# SCH_Timer_2026-05-08.net
KiCad netlist of a schematic drawn in EasyEDA
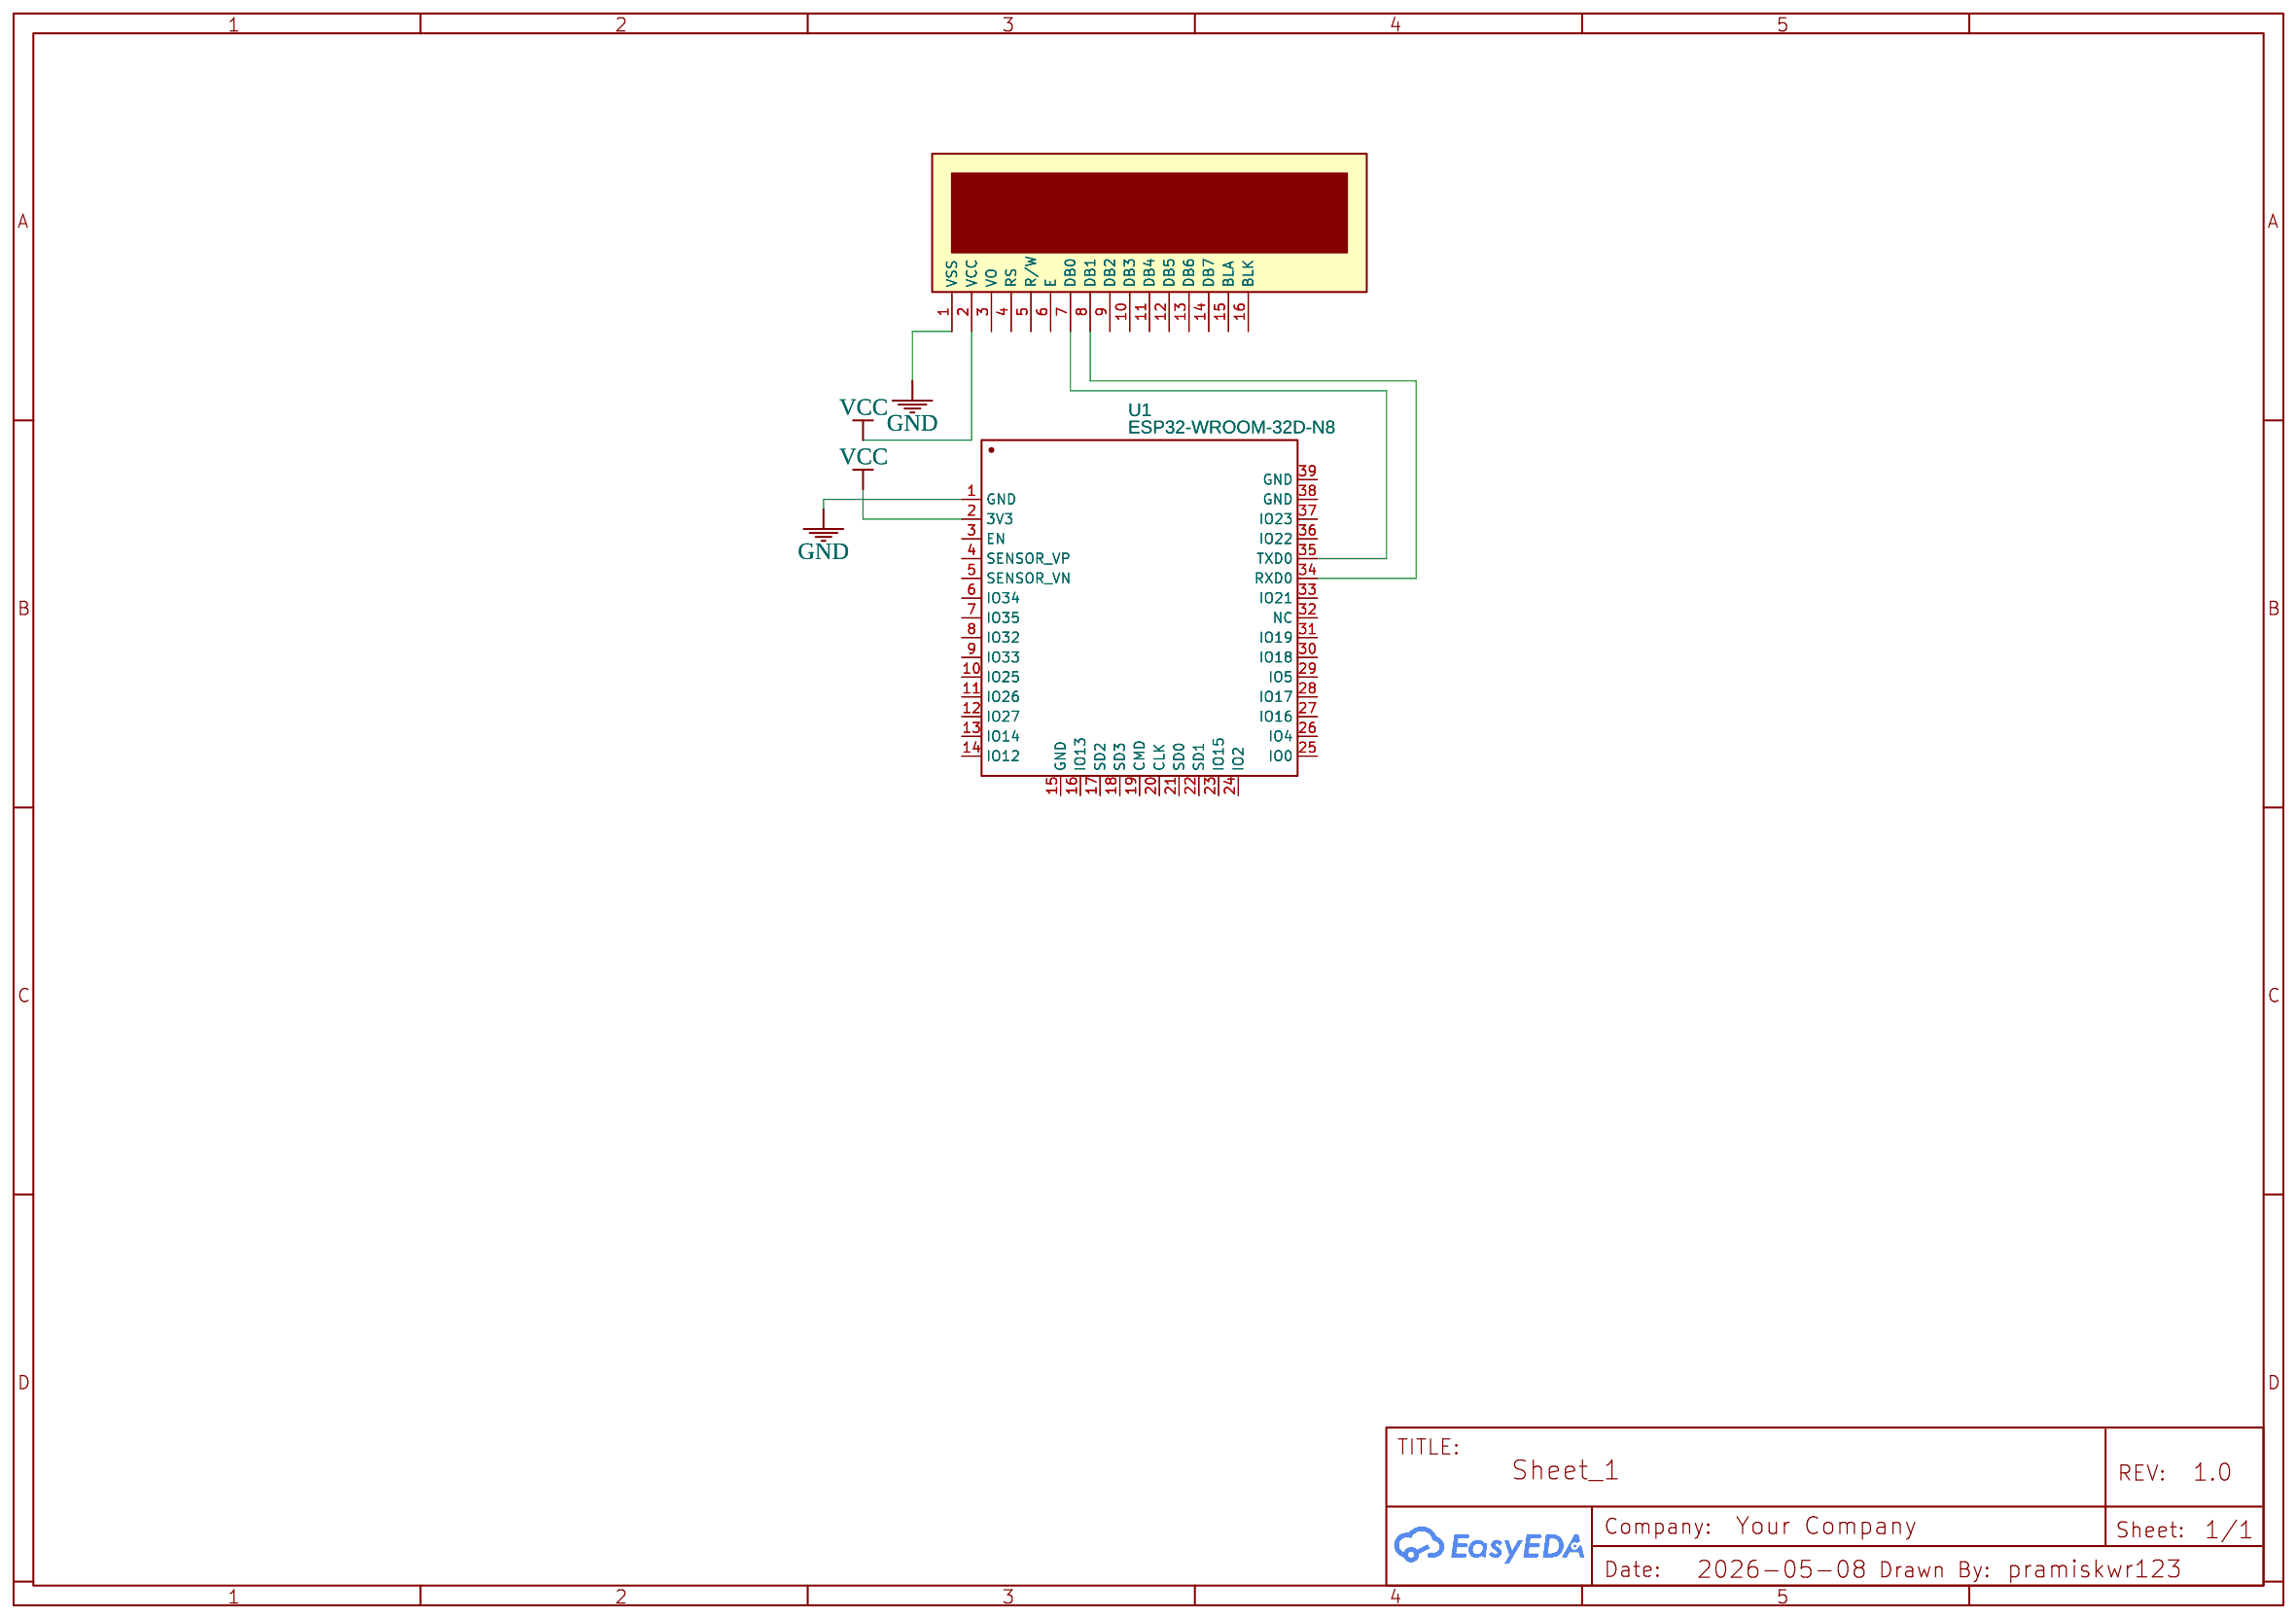
[diagram p0: schematic sheet]

(export (version "E")
  (design (tool "Eeschema 10.0.6"))
  (components
    (comp (ref "LCD1")
      (value "LCD1602")
      (fields
        (field (name "Manufacturer Part") "LCM1602K-NSW-BBW")
        (field (name "Manufacturer") "LONTECH(厦门龙特)")
      )
      (libsource (lib "") (part "LCD1602"))
    )
    (comp (ref "U1")
      (value "ESP32-WROOM-32D-N8")
      (fields (field (name "Manufacturer Part") "ESP32-WROOM-32D-N8-被合并"))
      (libsource (lib "") (part "ESP32-WROOM-32D-N8"))
    )
  )
  (nets
    (net (code "1") (name "GND") (class "Default")
      (node (ref "LCD1") (pin "1") (pinfunction "VSS_1") (pintype "unspecified"))
      (node (ref "U1") (pin "1") (pinfunction "GND_1") (pintype "unspecified"))
    )
    (net (code "2") (name "Net-(LCD1-DB0)") (class "Default")
      (node (ref "LCD1") (pin "7") (pinfunction "DB0_7") (pintype "unspecified"))
      (node (ref "U1") (pin "35") (pinfunction "TXD0_35") (pintype "unspecified"))
    )
    (net (code "3") (name "Net-(LCD1-DB1)") (class "Default")
      (node (ref "LCD1") (pin "8") (pinfunction "DB1_8") (pintype "unspecified"))
      (node (ref "U1") (pin "34") (pinfunction "RXD0_34") (pintype "unspecified"))
    )
    (net (code "4") (name "VCC") (class "Default")
      (node (ref "LCD1") (pin "2") (pinfunction "VCC_2") (pintype "unspecified"))
      (node (ref "U1") (pin "2") (pinfunction "3V3_2") (pintype "unspecified"))
    )
    (net (code "5") (name "unconnected-(LCD1-BLA-Pad15)") (class "Default")
      (node (ref "LCD1") (pin "15") (pinfunction "BLA_15") (pintype "unspecified"))
    )
    (net (code "6") (name "unconnected-(LCD1-BLK-Pad16)") (class "Default")
      (node (ref "LCD1") (pin "16") (pinfunction "BLK_16") (pintype "unspecified"))
    )
    (net (code "7") (name "unconnected-(LCD1-DB2-Pad9)") (class "Default")
      (node (ref "LCD1") (pin "9") (pinfunction "DB2_9") (pintype "unspecified"))
    )
    (net (code "8") (name "unconnected-(LCD1-DB3-Pad10)") (class "Default")
      (node (ref "LCD1") (pin "10") (pinfunction "DB3_10") (pintype "unspecified"))
    )
    (net (code "9") (name "unconnected-(LCD1-DB4-Pad11)") (class "Default")
      (node (ref "LCD1") (pin "11") (pinfunction "DB4_11") (pintype "unspecified"))
    )
    (net (code "10") (name "unconnected-(LCD1-DB5-Pad12)") (class "Default")
      (node (ref "LCD1") (pin "12") (pinfunction "DB5_12") (pintype "unspecified"))
    )
    (net (code "11") (name "unconnected-(LCD1-DB6-Pad13)") (class "Default")
      (node (ref "LCD1") (pin "13") (pinfunction "DB6_13") (pintype "unspecified"))
    )
    (net (code "12") (name "unconnected-(LCD1-DB7-Pad14)") (class "Default")
      (node (ref "LCD1") (pin "14") (pinfunction "DB7_14") (pintype "unspecified"))
    )
    (net (code "13") (name "unconnected-(LCD1-E-Pad6)") (class "Default")
      (node (ref "LCD1") (pin "6") (pinfunction "E_6") (pintype "unspecified"))
    )
    (net (code "14") (name "unconnected-(LCD1-RS-Pad4)") (class "Default")
      (node (ref "LCD1") (pin "4") (pinfunction "RS_4") (pintype "unspecified"))
    )
    (net (code "15") (name "unconnected-(LCD1-R{slash}W-Pad5)") (class "Default")
      (node (ref "LCD1") (pin "5") (pinfunction "R/W_5") (pintype "unspecified"))
    )
    (net (code "16") (name "unconnected-(LCD1-VO-Pad3)") (class "Default")
      (node (ref "LCD1") (pin "3") (pinfunction "VO_3") (pintype "unspecified"))
    )
    (net (code "17") (name "unconnected-(U1-CLK-Pad20)") (class "Default")
      (node (ref "U1") (pin "20") (pinfunction "CLK_20") (pintype "unspecified"))
    )
    (net (code "18") (name "unconnected-(U1-CMD-Pad19)") (class "Default")
      (node (ref "U1") (pin "19") (pinfunction "CMD_19") (pintype "unspecified"))
    )
    (net (code "19") (name "unconnected-(U1-EN-Pad3)") (class "Default")
      (node (ref "U1") (pin "3") (pinfunction "EN_3") (pintype "unspecified"))
    )
    (net (code "20") (name "unconnected-(U1-GND-Pad15)") (class "Default")
      (node (ref "U1") (pin "15") (pinfunction "GND_15") (pintype "unspecified"))
    )
    (net (code "21") (name "unconnected-(U1-GND-Pad38)") (class "Default")
      (node (ref "U1") (pin "38") (pinfunction "GND_38") (pintype "unspecified"))
    )
    (net (code "22") (name "unconnected-(U1-GND-Pad39)") (class "Default")
      (node (ref "U1") (pin "39") (pinfunction "GND_39") (pintype "unspecified"))
    )
    (net (code "23") (name "unconnected-(U1-IO0-Pad25)") (class "Default")
      (node (ref "U1") (pin "25") (pinfunction "IO0_25") (pintype "unspecified"))
    )
    (net (code "24") (name "unconnected-(U1-IO2-Pad24)") (class "Default")
      (node (ref "U1") (pin "24") (pinfunction "IO2_24") (pintype "unspecified"))
    )
    (net (code "25") (name "unconnected-(U1-IO4-Pad26)") (class "Default")
      (node (ref "U1") (pin "26") (pinfunction "IO4_26") (pintype "unspecified"))
    )
    (net (code "26") (name "unconnected-(U1-IO5-Pad29)") (class "Default")
      (node (ref "U1") (pin "29") (pinfunction "IO5_29") (pintype "unspecified"))
    )
    (net (code "27") (name "unconnected-(U1-IO12-Pad14)") (class "Default")
      (node (ref "U1") (pin "14") (pinfunction "IO12_14") (pintype "unspecified"))
    )
    (net (code "28") (name "unconnected-(U1-IO13-Pad16)") (class "Default")
      (node (ref "U1") (pin "16") (pinfunction "IO13_16") (pintype "unspecified"))
    )
    (net (code "29") (name "unconnected-(U1-IO14-Pad13)") (class "Default")
      (node (ref "U1") (pin "13") (pinfunction "IO14_13") (pintype "unspecified"))
    )
    (net (code "30") (name "unconnected-(U1-IO15-Pad23)") (class "Default")
      (node (ref "U1") (pin "23") (pinfunction "IO15_23") (pintype "unspecified"))
    )
    (net (code "31") (name "unconnected-(U1-IO16-Pad27)") (class "Default")
      (node (ref "U1") (pin "27") (pinfunction "IO16_27") (pintype "unspecified"))
    )
    (net (code "32") (name "unconnected-(U1-IO17-Pad28)") (class "Default")
      (node (ref "U1") (pin "28") (pinfunction "IO17_28") (pintype "unspecified"))
    )
    (net (code "33") (name "unconnected-(U1-IO18-Pad30)") (class "Default")
      (node (ref "U1") (pin "30") (pinfunction "IO18_30") (pintype "unspecified"))
    )
    (net (code "34") (name "unconnected-(U1-IO19-Pad31)") (class "Default")
      (node (ref "U1") (pin "31") (pinfunction "IO19_31") (pintype "unspecified"))
    )
    (net (code "35") (name "unconnected-(U1-IO21-Pad33)") (class "Default")
      (node (ref "U1") (pin "33") (pinfunction "IO21_33") (pintype "unspecified"))
    )
    (net (code "36") (name "unconnected-(U1-IO22-Pad36)") (class "Default")
      (node (ref "U1") (pin "36") (pinfunction "IO22_36") (pintype "unspecified"))
    )
    (net (code "37") (name "unconnected-(U1-IO23-Pad37)") (class "Default")
      (node (ref "U1") (pin "37") (pinfunction "IO23_37") (pintype "unspecified"))
    )
    (net (code "38") (name "unconnected-(U1-IO25-Pad10)") (class "Default")
      (node (ref "U1") (pin "10") (pinfunction "IO25_10") (pintype "unspecified"))
    )
    (net (code "39") (name "unconnected-(U1-IO26-Pad11)") (class "Default")
      (node (ref "U1") (pin "11") (pinfunction "IO26_11") (pintype "unspecified"))
    )
    (net (code "40") (name "unconnected-(U1-IO27-Pad12)") (class "Default")
      (node (ref "U1") (pin "12") (pinfunction "IO27_12") (pintype "unspecified"))
    )
    (net (code "41") (name "unconnected-(U1-IO32-Pad8)") (class "Default")
      (node (ref "U1") (pin "8") (pinfunction "IO32_8") (pintype "unspecified"))
    )
    (net (code "42") (name "unconnected-(U1-IO33-Pad9)") (class "Default")
      (node (ref "U1") (pin "9") (pinfunction "IO33_9") (pintype "unspecified"))
    )
    (net (code "43") (name "unconnected-(U1-IO34-Pad6)") (class "Default")
      (node (ref "U1") (pin "6") (pinfunction "IO34_6") (pintype "unspecified"))
    )
    (net (code "44") (name "unconnected-(U1-IO35-Pad7)") (class "Default")
      (node (ref "U1") (pin "7") (pinfunction "IO35_7") (pintype "unspecified"))
    )
    (net (code "45") (name "unconnected-(U1-NC-Pad32)") (class "Default")
      (node (ref "U1") (pin "32") (pinfunction "NC_32") (pintype "unspecified"))
    )
    (net (code "46") (name "unconnected-(U1-SD0-Pad21)") (class "Default")
      (node (ref "U1") (pin "21") (pinfunction "SD0_21") (pintype "unspecified"))
    )
    (net (code "47") (name "unconnected-(U1-SD1-Pad22)") (class "Default")
      (node (ref "U1") (pin "22") (pinfunction "SD1_22") (pintype "unspecified"))
    )
    (net (code "48") (name "unconnected-(U1-SD2-Pad17)") (class "Default")
      (node (ref "U1") (pin "17") (pinfunction "SD2_17") (pintype "unspecified"))
    )
    (net (code "49") (name "unconnected-(U1-SD3-Pad18)") (class "Default")
      (node (ref "U1") (pin "18") (pinfunction "SD3_18") (pintype "unspecified"))
    )
    (net (code "50") (name "unconnected-(U1-SENSOR_VN-Pad5)") (class "Default")
      (node (ref "U1") (pin "5") (pinfunction "SENSOR_VN_5") (pintype "unspecified"))
    )
    (net (code "51") (name "unconnected-(U1-SENSOR_VP-Pad4)") (class "Default")
      (node (ref "U1") (pin "4") (pinfunction "SENSOR_VP_4") (pintype "unspecified"))
    )
  )
)
